# sensor.net
KiCad netlist of a schematic drawn in Altium Designer
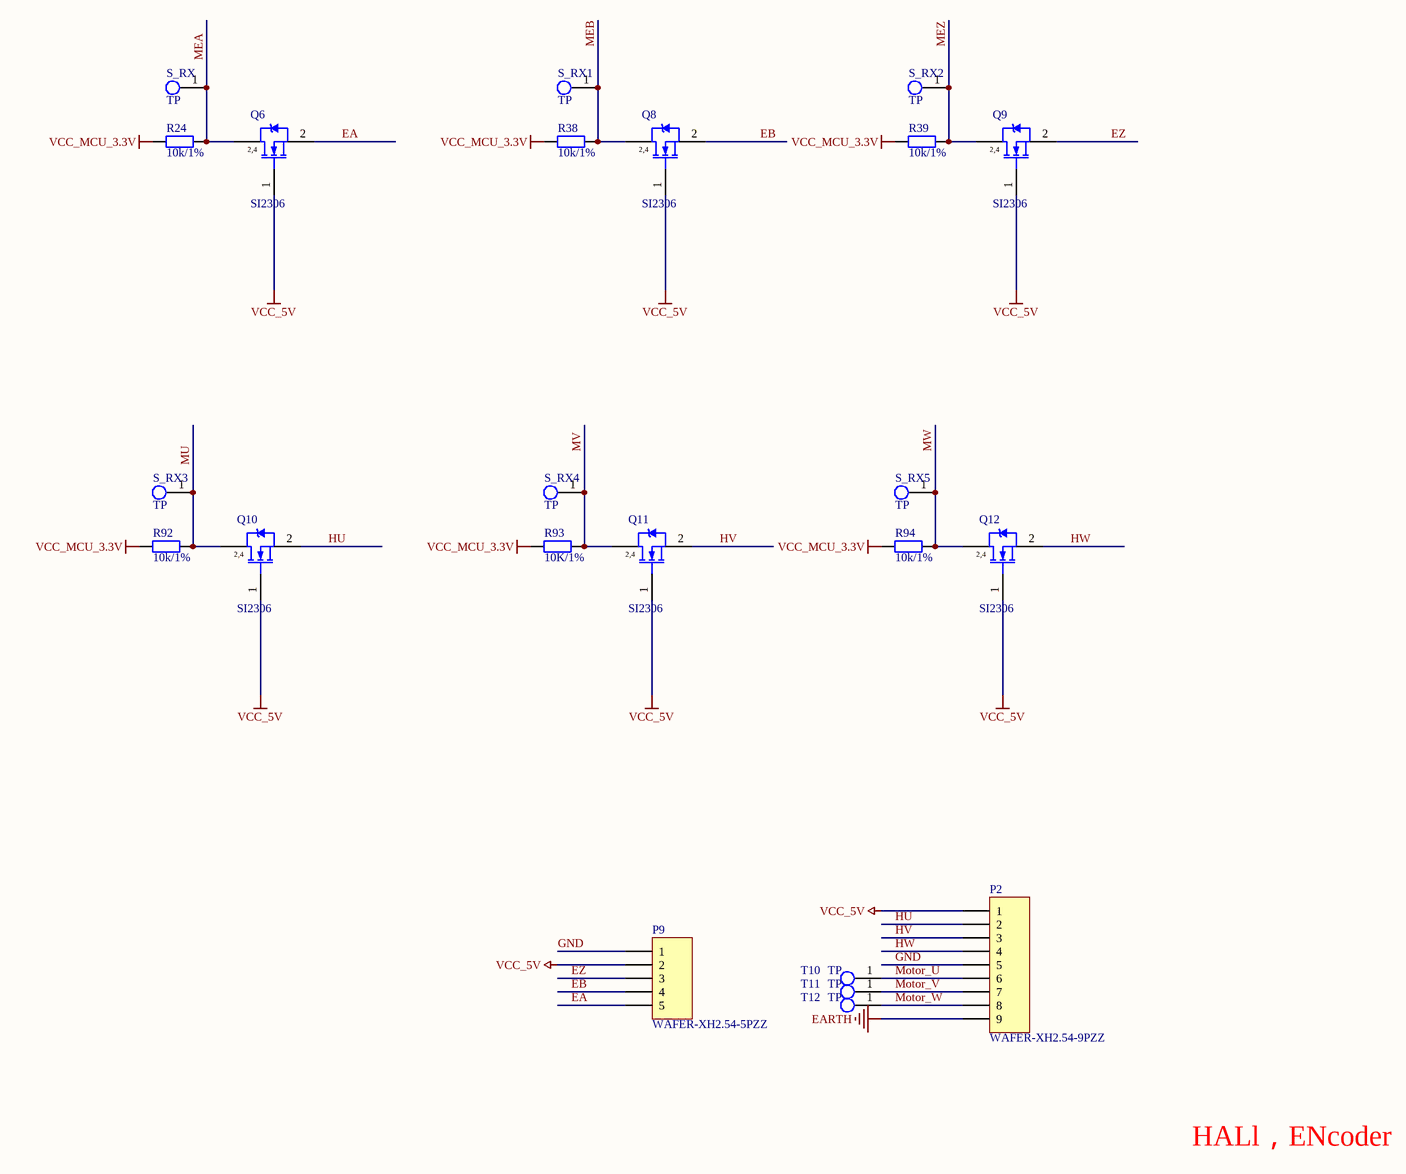
[diagram p0: sensor.SchDoc]

(export (version "E")
  (design (tool "Eeschema 10.0.6"))
  (components
    (comp (ref "P2")
      (value "WAFER-XH2.54-9PZZ")
      (footprint "XA2.5-9P")
      (description "Header, 9-Pin")
      (libsource (lib "Miscellaneous Connectors") (part "Header 9"))
    )
    (comp (ref "P9")
      (value "WAFER-XH2.54-5PZZ")
      (footprint "XA2.5-5P")
      (description "Header, 5-Pin")
      (libsource (lib "Miscellaneous Connectors") (part "Header 5"))
    )
    (comp (ref "Q6")
      (value "SI2306")
      (footprint "Pcblib_20110825:SOT23-3")
      (description "BUK92150-55A")
      (libsource (lib "Schlib1") (part "BUK92150-55A"))
    )
    (comp (ref "Q8")
      (value "SI2306")
      (footprint "SOT23-3")
      (description "BUK92150-55A")
      (libsource (lib "Schlib1") (part "BUK92150-55A"))
    )
    (comp (ref "Q9")
      (value "SI2306")
      (footprint "Pcblib_20110825:SOT23-3")
      (description "BUK92150-55A")
      (libsource (lib "Schlib1") (part "BUK92150-55A"))
    )
    (comp (ref "Q10")
      (value "SI2306")
      (footprint "Pcblib_20110825:SOT23-3")
      (description "BUK92150-55A")
      (libsource (lib "Schlib1") (part "BUK92150-55A"))
    )
    (comp (ref "Q11")
      (value "SI2306")
      (footprint "Pcblib_20110825:SOT23-3")
      (description "BUK92150-55A")
      (libsource (lib "Schlib1") (part "BUK92150-55A"))
    )
    (comp (ref "Q12")
      (value "SI2306")
      (footprint "Pcblib_20110825:SOT23-3")
      (description "BUK92150-55A")
      (libsource (lib "Schlib1") (part "BUK92150-55A"))
    )
    (comp (ref "R24")
      (value "10k/1%")
      (footprint "Pcblib_20110825:0603R")
      (description "Resistor")
      (libsource (lib "Miscellaneous Devices") (part "Res2"))
    )
    (comp (ref "R38")
      (value "10k/1%")
      (footprint "Pcblib_20110825:0603R")
      (description "Resistor")
      (libsource (lib "Miscellaneous Devices") (part "Res2"))
    )
    (comp (ref "R39")
      (value "10k/1%")
      (footprint "Pcblib_20110825:0603R")
      (description "Resistor")
      (libsource (lib "Miscellaneous Devices") (part "Res2"))
    )
    (comp (ref "R92")
      (value "10k/1%")
      (footprint "Pcblib_20110825:0603R")
      (description "Resistor")
      (libsource (lib "Miscellaneous Devices") (part "Res2"))
    )
    (comp (ref "R93")
      (value "10K/1%")
      (footprint "Pcblib_20110825:0603R")
      (description "Resistor")
      (libsource (lib "Miscellaneous Devices") (part "Res2"))
    )
    (comp (ref "R94")
      (value "10k/1%")
      (footprint "Pcblib_20110825:0603R")
      (description "Resistor")
      (libsource (lib "Miscellaneous Devices") (part "Res2"))
    )
    (comp (ref "S_RX")
      (value "TP")
      (footprint "Pcblib_20110825:TPD")
      (libsource (lib "Schlib_20110825") (part "TP"))
    )
    (comp (ref "S_RX1")
      (value "TP")
      (footprint "Pcblib_20110825:TPD")
      (libsource (lib "Schlib_20110825") (part "TP"))
    )
    (comp (ref "S_RX2")
      (value "TP")
      (footprint "Pcblib_20110825:TPD")
      (libsource (lib "Schlib_20110825") (part "TP"))
    )
    (comp (ref "S_RX3")
      (value "TP")
      (footprint "Pcblib_20110825:TPD")
      (libsource (lib "Schlib_20110825") (part "TP"))
    )
    (comp (ref "S_RX4")
      (value "TP")
      (footprint "Pcblib_20110825:TPD")
      (libsource (lib "Schlib_20110825") (part "TP"))
    )
    (comp (ref "S_RX5")
      (value "TP")
      (footprint "Pcblib_20110825:TPD")
      (libsource (lib "Schlib_20110825") (part "TP"))
    )
    (comp (ref "T10") (value "TP") (footprint "TPD") (libsource (lib "Schlib_20110825") (part "TP")))
    (comp (ref "T11") (value "TP") (footprint "TPD") (libsource (lib "Schlib_20110825") (part "TP")))
    (comp (ref "T12") (value "TP") (footprint "TPD") (libsource (lib "Schlib_20110825") (part "TP")))
  )
  (nets
    (net (code "1") (name "/EA") (class "Default")
      (node (ref "P9") (pin "5") (pinfunction "5_5") (pintype "passive"))
      (node (ref "Q6") (pin "2") (pinfunction "S_2") (pintype "passive"))
    )
    (net (code "2") (name "/EB") (class "Default")
      (node (ref "P9") (pin "4") (pinfunction "4_4") (pintype "passive"))
      (node (ref "Q8") (pin "2") (pinfunction "S_2") (pintype "passive"))
    )
    (net (code "3") (name "/EZ") (class "Default")
      (node (ref "P9") (pin "3") (pinfunction "3_3") (pintype "passive"))
      (node (ref "Q9") (pin "2") (pinfunction "S_2") (pintype "passive"))
    )
    (net (code "4") (name "/GND") (class "Default")
      (node (ref "P2") (pin "5") (pinfunction "5_5") (pintype "passive"))
      (node (ref "P9") (pin "1") (pinfunction "1_1") (pintype "passive"))
    )
    (net (code "5") (name "/HU") (class "Default")
      (node (ref "P2") (pin "2") (pinfunction "2_2") (pintype "passive"))
      (node (ref "Q10") (pin "2") (pinfunction "S_2") (pintype "passive"))
    )
    (net (code "6") (name "/HV") (class "Default")
      (node (ref "P2") (pin "3") (pinfunction "3_3") (pintype "passive"))
      (node (ref "Q11") (pin "2") (pinfunction "S_2") (pintype "passive"))
    )
    (net (code "7") (name "/HW") (class "Default")
      (node (ref "P2") (pin "4") (pinfunction "4_4") (pintype "passive"))
      (node (ref "Q12") (pin "2") (pinfunction "S_2") (pintype "passive"))
    )
    (net (code "8") (name "/MEA") (class "Default")
      (node (ref "Q6") (pin "3") (pinfunction "D_3") (pintype "passive"))
      (node (ref "R24") (pin "2") (pinfunction "2_2") (pintype "passive"))
      (node (ref "S_RX") (pin "1") (pintype "passive"))
    )
    (net (code "9") (name "/MEB") (class "Default")
      (node (ref "Q8") (pin "3") (pinfunction "D_3") (pintype "passive"))
      (node (ref "R38") (pin "2") (pinfunction "2_2") (pintype "passive"))
      (node (ref "S_RX1") (pin "1") (pintype "passive"))
    )
    (net (code "10") (name "/MEZ") (class "Default")
      (node (ref "Q9") (pin "3") (pinfunction "D_3") (pintype "passive"))
      (node (ref "R39") (pin "2") (pinfunction "2_2") (pintype "passive"))
      (node (ref "S_RX2") (pin "1") (pintype "passive"))
    )
    (net (code "11") (name "/MU") (class "Default")
      (node (ref "Q10") (pin "3") (pinfunction "D_3") (pintype "passive"))
      (node (ref "R92") (pin "2") (pinfunction "2_2") (pintype "passive"))
      (node (ref "S_RX3") (pin "1") (pintype "passive"))
    )
    (net (code "12") (name "/MV") (class "Default")
      (node (ref "Q11") (pin "3") (pinfunction "D_3") (pintype "passive"))
      (node (ref "R93") (pin "2") (pinfunction "2_2") (pintype "passive"))
      (node (ref "S_RX4") (pin "1") (pintype "passive"))
    )
    (net (code "13") (name "/MW") (class "Default")
      (node (ref "Q12") (pin "3") (pinfunction "D_3") (pintype "passive"))
      (node (ref "R94") (pin "2") (pinfunction "2_2") (pintype "passive"))
      (node (ref "S_RX5") (pin "1") (pintype "passive"))
    )
    (net (code "14") (name "/Motor_U") (class "Default")
      (node (ref "P2") (pin "6") (pinfunction "6_6") (pintype "passive"))
      (node (ref "T10") (pin "1") (pintype "passive"))
    )
    (net (code "15") (name "/Motor_V") (class "Default")
      (node (ref "P2") (pin "7") (pinfunction "7_7") (pintype "passive"))
      (node (ref "T11") (pin "1") (pintype "passive"))
    )
    (net (code "16") (name "/Motor_W") (class "Default")
      (node (ref "P2") (pin "8") (pinfunction "8_8") (pintype "passive"))
      (node (ref "T12") (pin "1") (pintype "passive"))
    )
    (net (code "17") (name "EARTH") (class "Default")
      (node (ref "P2") (pin "9") (pinfunction "9_9") (pintype "passive"))
    )
    (net (code "18") (name "VCC_5V") (class "Default")
      (node (ref "P2") (pin "1") (pinfunction "1_1") (pintype "passive"))
      (node (ref "P9") (pin "2") (pinfunction "2_2") (pintype "passive"))
      (node (ref "Q10") (pin "1") (pinfunction "G_1") (pintype "passive"))
      (node (ref "Q11") (pin "1") (pinfunction "G_1") (pintype "passive"))
      (node (ref "Q12") (pin "1") (pinfunction "G_1") (pintype "passive"))
      (node (ref "Q6") (pin "1") (pinfunction "G_1") (pintype "passive"))
      (node (ref "Q8") (pin "1") (pinfunction "G_1") (pintype "passive"))
      (node (ref "Q9") (pin "1") (pinfunction "G_1") (pintype "passive"))
    )
    (net (code "19") (name "VCC_MCU_3.3V") (class "Default")
      (node (ref "R24") (pin "1") (pinfunction "1_1") (pintype "passive"))
      (node (ref "R38") (pin "1") (pinfunction "1_1") (pintype "passive"))
      (node (ref "R39") (pin "1") (pinfunction "1_1") (pintype "passive"))
      (node (ref "R92") (pin "1") (pinfunction "1_1") (pintype "passive"))
      (node (ref "R93") (pin "1") (pinfunction "1_1") (pintype "passive"))
      (node (ref "R94") (pin "1") (pinfunction "1_1") (pintype "passive"))
    )
  )
)
